# RX.net
KiCad netlist of a schematic drawn in Altium Designer
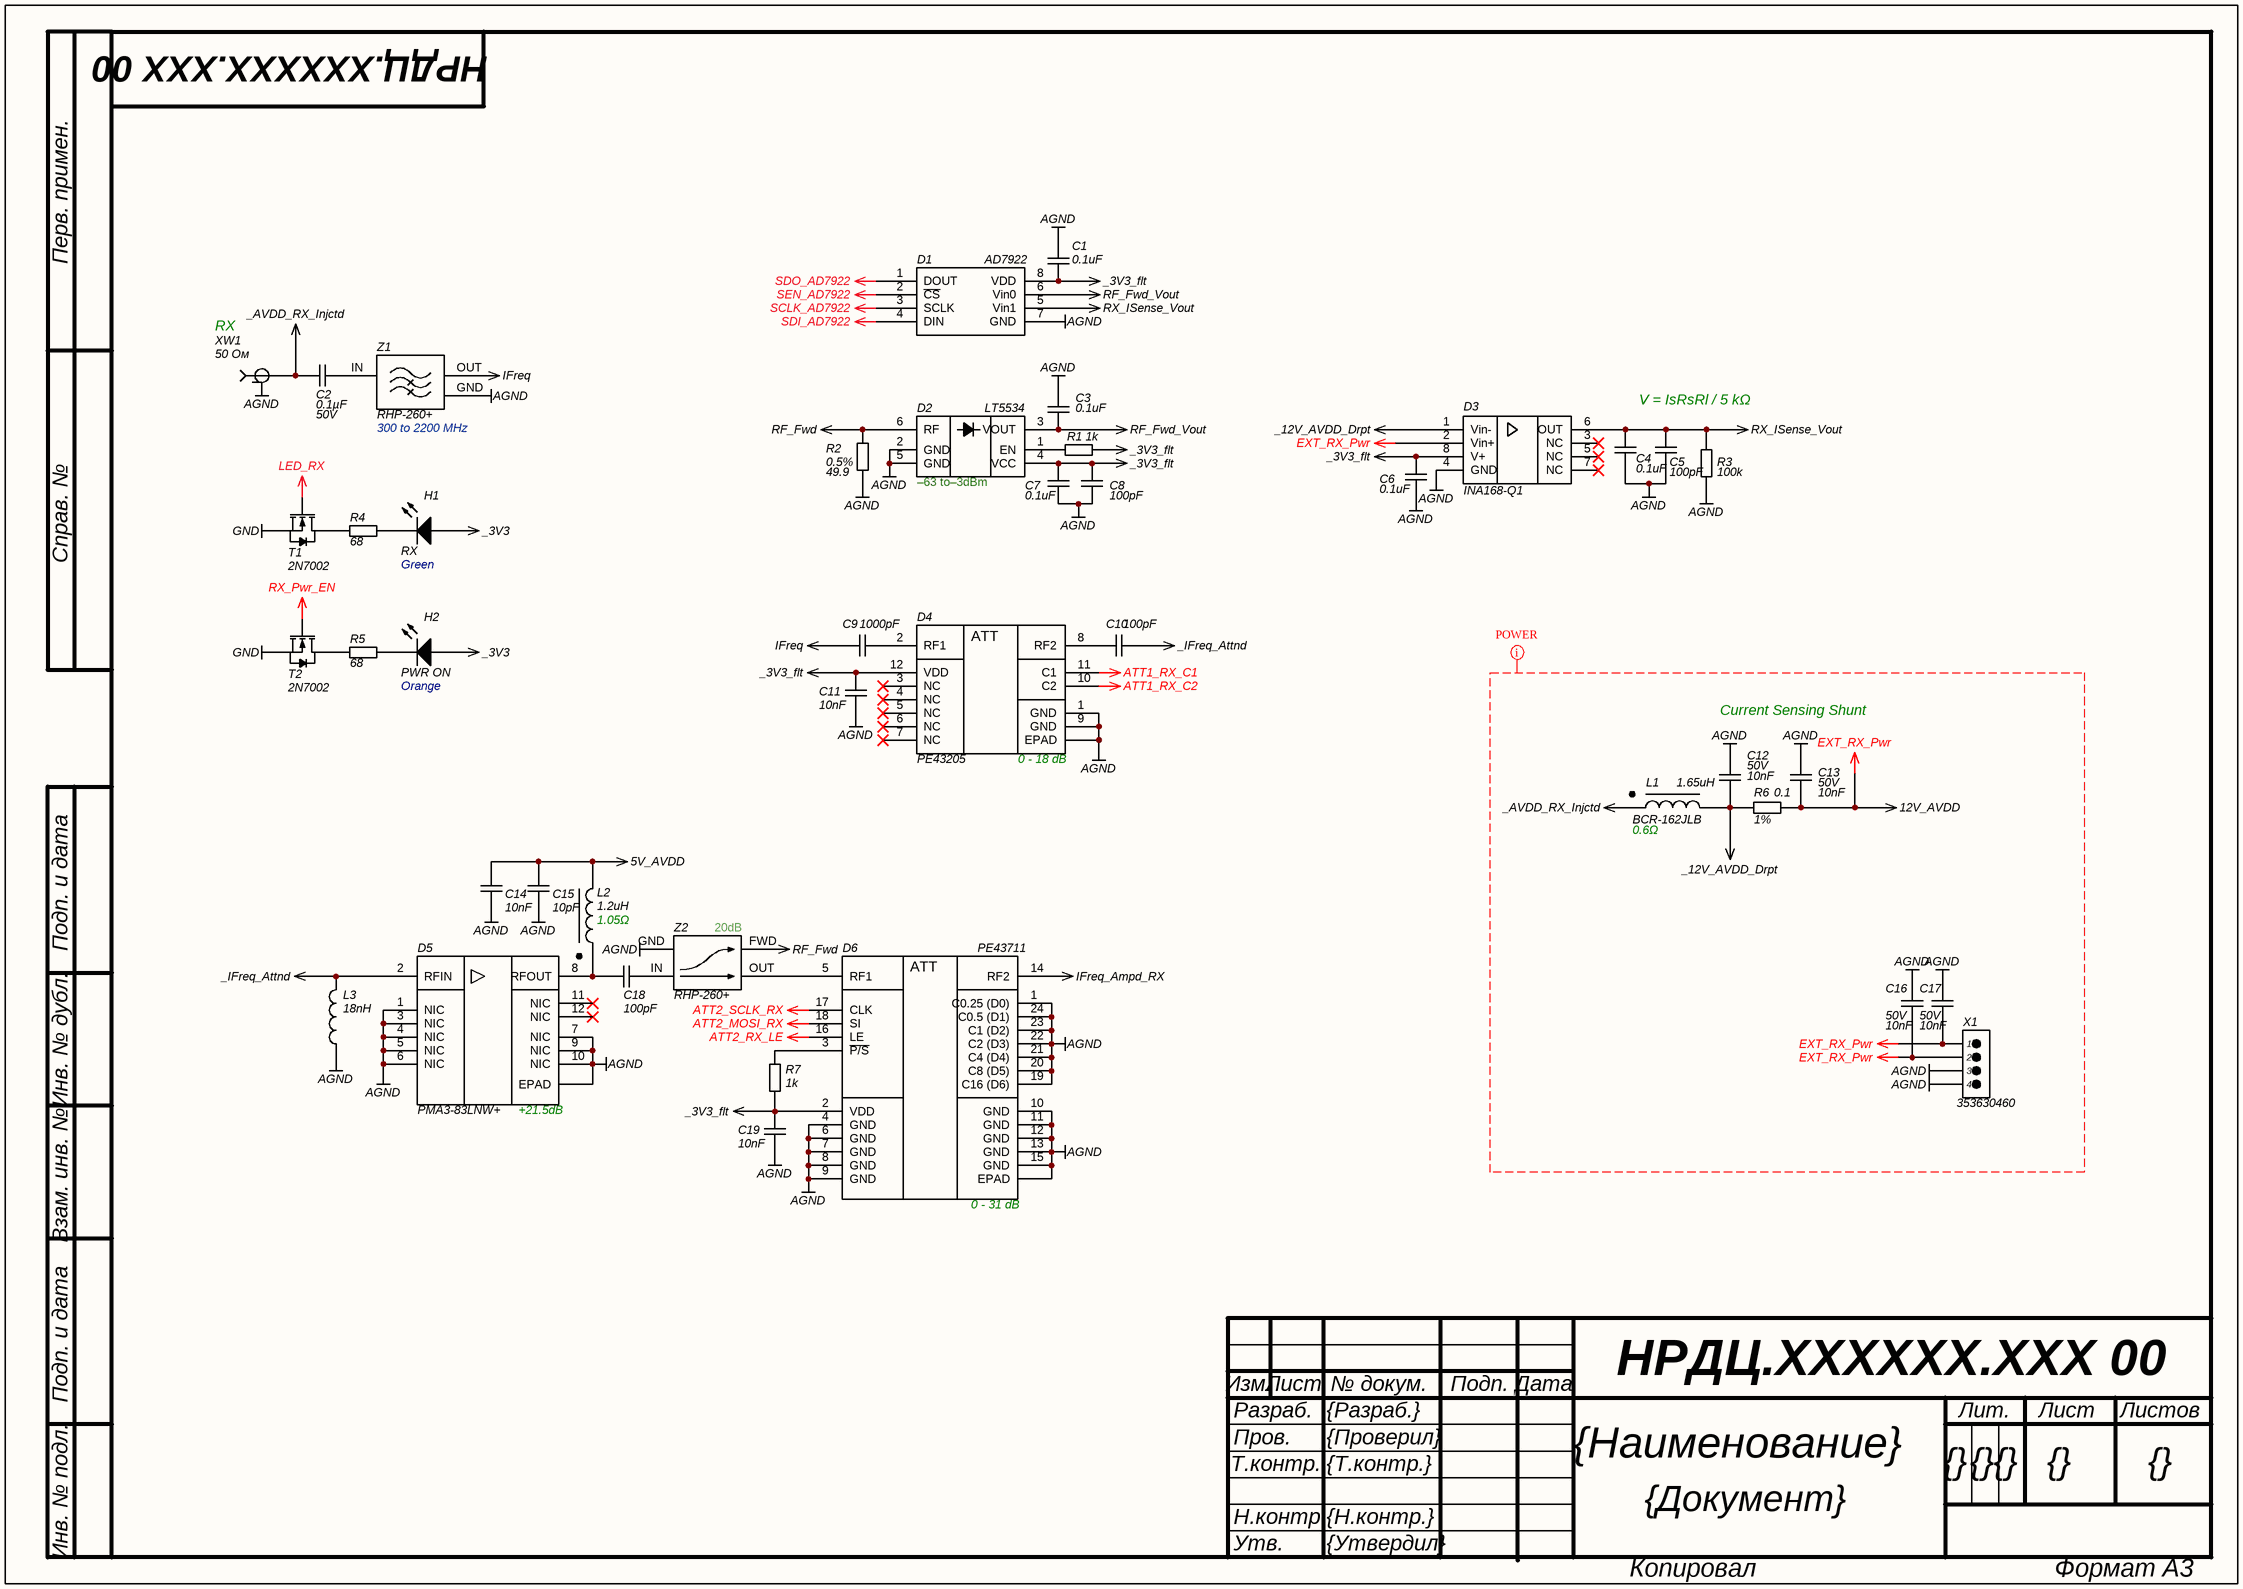
[diagram p0: RX.SchDoc]

(export (version "E")
  (design (tool "Eeschema 10.0.6"))
  (components
    (comp (ref "C1")
      (value "0.1uF")
      (footprint "C0402")
      (description "SMD Capacitor")
      (fields (field (name "MANUFACTURER") "Murata") (field (name "TOLERANCE") "10%"))
      (libsource (lib "Kintex_SDR") (part "CAP"))
    )
    (comp (ref "C2")
      (value "0.1µF")
      (footprint "C1206")
      (description "SMD Capacitor")
      (fields
        (field (name "MANUFACTURER") "Murata")
        (field (name "TOLERANCE") "5%")
        (field (name "VOLTAGE") "50V")
      )
      (libsource (lib "Kintex_SDR") (part "CAP"))
    )
    (comp (ref "C3")
      (value "0.1uF")
      (footprint "C0402")
      (description "SMD Capacitor")
      (fields (field (name "MANUFACTURER") "Murata") (field (name "TOLERANCE") "10%"))
      (libsource (lib "Kintex_SDR") (part "CAP"))
    )
    (comp (ref "C4")
      (value "0.1uF")
      (footprint "C0402")
      (description "SMD Capacitor")
      (fields (field (name "MANUFACTURER") "Murata") (field (name "TOLERANCE") "10%"))
      (libsource (lib "Kintex_SDR") (part "CAP"))
    )
    (comp (ref "C5")
      (value "100pF")
      (footprint "C0402")
      (description "SMD Capacitor")
      (fields (field (name "MANUFACTURER") "Murata") (field (name "TOLERANCE") "1%"))
      (libsource (lib "Kintex_SDR") (part "CAP"))
    )
    (comp (ref "C6")
      (value "0.1uF")
      (footprint "C0402")
      (description "SMD Capacitor")
      (fields (field (name "MANUFACTURER") "Murata") (field (name "TOLERANCE") "10%"))
      (libsource (lib "Kintex_SDR") (part "CAP"))
    )
    (comp (ref "C7")
      (value "0.1uF")
      (footprint "C0402")
      (description "SMD Capacitor")
      (fields (field (name "MANUFACTURER") "Murata") (field (name "TOLERANCE") "10%"))
      (libsource (lib "Kintex_SDR") (part "CAP"))
    )
    (comp (ref "C8")
      (value "100pF")
      (footprint "C0402")
      (description "SMD Capacitor")
      (fields (field (name "MANUFACTURER") "Murata") (field (name "TOLERANCE") "1%"))
      (libsource (lib "Kintex_SDR") (part "CAP"))
    )
    (comp (ref "C9")
      (value "1000pF")
      (footprint "C0402")
      (description "SMD Capacitor")
      (fields (field (name "MANUFACTURER") "Murata") (field (name "TOLERANCE") "5%"))
      (libsource (lib "Kintex_SDR") (part "CAP"))
    )
    (comp (ref "C10")
      (value "100pF")
      (footprint "C0402")
      (description "SMD Capacitor")
      (fields (field (name "MANUFACTURER") "Murata") (field (name "TOLERANCE") "1%"))
      (libsource (lib "Kintex_SDR") (part "CAP"))
    )
    (comp (ref "C11")
      (value "10nF")
      (footprint "C0402")
      (description "SMD Capacitor")
      (fields (field (name "MANUFACTURER") "Murata") (field (name "TOLERANCE") "10%"))
      (libsource (lib "Kintex_SDR") (part "CAP"))
    )
    (comp (ref "C12")
      (value "10nF")
      (footprint "C0402")
      (description "SMD Capacitor")
      (fields
        (field (name "MANUFACTURER") "Murata")
        (field (name "TOLERANCE") "5%")
        (field (name "VOLTAGE") "50V")
      )
      (libsource (lib "Kintex_SDR") (part "CAP"))
    )
    (comp (ref "C13")
      (value "10nF")
      (footprint "C0402")
      (description "SMD Capacitor")
      (fields
        (field (name "MANUFACTURER") "Murata")
        (field (name "TOLERANCE") "5%")
        (field (name "VOLTAGE") "50V")
      )
      (libsource (lib "Kintex_SDR") (part "CAP"))
    )
    (comp (ref "C14")
      (value "10nF")
      (footprint "C0402")
      (description "SMD Capacitor")
      (fields (field (name "MANUFACTURER") "Murata") (field (name "TOLERANCE") "10%"))
      (libsource (lib "Kintex_SDR") (part "CAP"))
    )
    (comp (ref "C15")
      (value "10pF")
      (footprint "C0402")
      (description "SMD Capacitor")
      (fields (field (name "MANUFACTURER") "Murata") (field (name "TOLERANCE") "1%"))
      (libsource (lib "Kintex_SDR") (part "CAP"))
    )
    (comp (ref "C16")
      (value "10nF")
      (footprint "C0402")
      (description "SMD Capacitor")
      (fields
        (field (name "MANUFACTURER") "Murata")
        (field (name "TOLERANCE") "5%")
        (field (name "VOLTAGE") "50V")
      )
      (libsource (lib "Kintex_SDR") (part "CAP"))
    )
    (comp (ref "C17")
      (value "10nF")
      (footprint "C0402")
      (description "SMD Capacitor")
      (fields
        (field (name "MANUFACTURER") "Murata")
        (field (name "TOLERANCE") "5%")
        (field (name "VOLTAGE") "50V")
      )
      (libsource (lib "Kintex_SDR") (part "CAP"))
    )
    (comp (ref "C18")
      (value "100pF")
      (footprint "C0402")
      (description "SMD Capacitor")
      (fields (field (name "MANUFACTURER") "Murata") (field (name "TOLERANCE") "1%"))
      (libsource (lib "Kintex_SDR") (part "CAP"))
    )
    (comp (ref "C19")
      (value "10nF")
      (footprint "C0402")
      (description "SMD Capacitor")
      (fields (field (name "MANUFACTURER") "Murata") (field (name "TOLERANCE") "10%"))
      (libsource (lib "Kintex_SDR") (part "CAP"))
    )
    (comp (ref "D1")
      (value "AD7922")
      (footprint "MSOP-8")
      (description "1 MSPS, 10-/12-Bit ADC")
      (fields (field (name "MANUFACTURER") "Analog Device") (field (name "VOLTAGE") "2.35 V to 5.25 V"))
      (libsource (lib "Kintex_SDR") (part "AD79x2"))
    )
    (comp (ref "D2")
      (value "LT5534")
      (footprint "DBLib:SC70")
      (description "50MHz to 3GHz monolithic RF power\r\ndetector")
      (fields
        (field (name "MANUFACTURER") "Linear Technology")
        (field (name "VOLTAGE") "Single 2.7V to 5.25V")
        (field (name "RF INPUT POWER RANGE") "–63 to–3dBm")
      )
      (libsource (lib "DBLib") (part "LT5534"))
    )
    (comp (ref "D3")
      (value "INA168-Q1")
      (footprint "DBLib:TSSOP (8)")
      (description "Automotive-Grade, High-Side, Current-Output, Current-Shunt Monitor")
      (fields (field (name "MANUFACTURER") "Texas Instruments") (field (name "VOLTAGE") "2.7 V to 60 V"))
      (libsource (lib "DBLib") (part "INA168-Q1"))
    )
    (comp (ref "D4")
      (value "PE43205")
      (footprint "DBLib:QFN-12")
      (description "50Ω, HaRP™ technology-enhanced\r\nfast switching 2-bit RF Digital Step Attenuator")
      (fields (field (name "MANUFACTURER") "Peregrine Technical Solutions"))
      (libsource (lib "DBLib") (part "PE43205"))
    )
    (comp (ref "D5")
      (value "PMA3-83LNW+")
      (footprint "DQ1225")
      (description "PHEMT based wideband, low noise MMIC amplifier")
      (fields (field (name "MANUFACTURER") "Mini-Circuits"))
      (libsource (lib "DBLib") (part "PMA3-83LNW+"))
    )
    (comp (ref "D6")
      (value "PE43711")
      (footprint "QFN-24")
      (description "The PE43711 is a 50Ω, HaRP™ technology-enhanced, 7-bit RF digital step attenuator")
      (fields (field (name "MANUFACTURER") "Peregrine Technical Solutions"))
      (libsource (lib "DBLib") (part "PE43711"))
    )
    (comp (ref "H1")
      (value "RX")
      (footprint "LED")
      (description "CHIP LED LAMP")
      (fields (field (name "MANUFACTURER") "Kingbright") (field (name "COLOR") "Green"))
      (libsource (lib "DBLib") (part "LED"))
    )
    (comp (ref "H2")
      (value "PWR ON")
      (footprint "LED")
      (description "CHIP LED LAMP")
      (fields (field (name "MANUFACTURER") "Kingbright") (field (name "COLOR") "Orange"))
      (libsource (lib "DBLib") (part "LED"))
    )
    (comp (ref "L1")
      (value "BCR-162JLB")
      (footprint "DBLib:BCR-162")
      (description "Broadband Conical Inductor")
      (fields
        (field (name "MANUFACTURER") "Coilcraft")
        (field (name "TOLERANCE") "±5%")
        (field (name "ALTIUM_VALUE") "1.65uH")
        (field (name "DCR") "0.6Ω")
      )
      (libsource (lib "DBLib") (part "Inductor_BCR"))
    )
    (comp (ref "L2")
      (value "1.2uH")
      (footprint "DBLib:BCR-122")
      (description "Broadband Conical Inductor")
      (fields
        (field (name "MANUFACTURER") "Coilcraft")
        (field (name "TOLERANCE") "±5%")
        (field (name "DCR") "1.05Ω")
      )
      (libsource (lib "DBLib") (part "Inductor_BCR"))
    )
    (comp (ref "L3")
      (value "18nH")
      (footprint "DBLib:L0603_HP")
      (description "Chip SMD Inductor")
      (fields (field (name "MANUFACTURER") "Coilcraft") (field (name "TOLERANCE") "5%"))
      (libsource (lib "DBLib") (part "Inductor RF"))
    )
    (comp (ref "R1")
      (value "1k")
      (footprint "R0402")
      (description "SMD Resistor")
      (fields (field (name "POWER") "0.062 Wt") (field (name "TOLERANCE") "5%"))
      (libsource (lib "Kintex_SDR") (part "RES"))
    )
    (comp (ref "R2")
      (value "49.9")
      (footprint "R0402")
      (description "SMD Resistor")
      (fields
        (field (name "POWER") "0.063 Wt")
        (field (name "TOLERANCE") "0.5%")
        (field (name "MANUFACTURER") "Panasonic Electronic Components")
      )
      (libsource (lib "") (part "RES_1"))
    )
    (comp (ref "R3")
      (value "100k")
      (footprint "R0402")
      (description "SMD Resistor")
      (fields (field (name "POWER") "1/5 Wt") (field (name "TOLERANCE") "1%"))
      (libsource (lib "") (part "RES_2"))
    )
    (comp (ref "R4")
      (value "68")
      (footprint "R0402")
      (description "SMD Resistor")
      (fields (field (name "POWER") "0.062 Wt") (field (name "TOLERANCE") "5%"))
      (libsource (lib "") (part "RES_3"))
    )
    (comp (ref "R5")
      (value "68")
      (footprint "R0402")
      (description "SMD Resistor")
      (fields (field (name "POWER") "0.062 Wt") (field (name "TOLERANCE") "5%"))
      (libsource (lib "Kintex_SDR") (part "RES"))
    )
    (comp (ref "R6")
      (value "0.1")
      (footprint "R0805")
      (description "SMD Resistor")
      (fields
        (field (name "POWER") "1/2 Wt")
        (field (name "TOLERANCE") "1%")
        (field (name "MANUFACTURER") "Panasonic Electronic Components")
      )
      (libsource (lib "Kintex_SDR") (part "RES"))
    )
    (comp (ref "R7")
      (value "1k")
      (footprint "R0402")
      (description "SMD Resistor")
      (fields (field (name "POWER") "0.062 Wt") (field (name "TOLERANCE") "5%"))
      (libsource (lib "") (part "RES_2"))
    )
    (comp (ref "T1")
      (value "2N7002")
      (footprint "SOT-23")
      (description "N-Channel MOSFET 2N7002")
      (fields (field (name "VOLTAGE") "60V"))
      (libsource (lib "Kintex_SDR") (part "2N7002"))
    )
    (comp (ref "T2")
      (value "2N7002")
      (footprint "SOT-23")
      (description "N-Channel MOSFET 2N7002")
      (fields (field (name "VOLTAGE") "60V"))
      (libsource (lib "Kintex_SDR") (part "2N7002"))
    )
    (comp (ref "X1")
      (value "353630460")
      (footprint "DBLib:CON_353630460")
      (description "2.00mm Pitch Sherlock Wire-to-Board Header, Right-Angle, with Positive Lock, 4 Circuits")
      (fields (field (name "MANUFACTURER") "Molex"))
      (libsource (lib "DBLib") (part "353630460"))
    )
    (comp (ref "XW1")
      (value "50 Ом")
      (footprint "MOLEX SD-73251-135 (Gold)")
      (description "50 Ohms, SMA Jack, Vertica")
      (fields (field (name "MANUFACTURER") "Molex"))
      (libsource (lib "DBLib") (part "RF Connector"))
    )
    (comp (ref "Z1")
      (value "RHP-260+")
      (footprint "GP731")
      (description "High Pass Filter")
      (fields (field (name "MANUFACTURER") "Mini-Circuits") (field (name "FREQUENCY") "300 to 2200 MHz"))
      (libsource (lib "DBLib") (part "RHP-260+"))
    )
    (comp (ref "Z2")
      (value "RHP-260+")
      (footprint "DBLib:AH202")
      (description "Directional Coupler")
      (fields (field (name "MANUFACTURER") "Mini-Circuits") (field (name "COUPLING") "20dB"))
      (libsource (lib "DBLib") (part "SYD-20-33+"))
    )
  )
  (nets
    (net (code "1") (name "5V_AVDD") (class "Default")
      (node (ref "C14") (pin "2") (pinfunction "2_2") (pintype "passive"))
      (node (ref "C15") (pin "2") (pinfunction "2_2") (pintype "passive"))
      (node (ref "L2") (pin "2") (pinfunction "2_2") (pintype "passive"))
    )
    (net (code "2") (name "12V_AVDD") (class "Default")
      (node (ref "C13") (pin "1") (pinfunction "1_1") (pintype "passive"))
      (node (ref "C16") (pin "2") (pinfunction "2_2") (pintype "passive"))
      (node (ref "C17") (pin "2") (pinfunction "2_2") (pintype "passive"))
      (node (ref "D3") (pin "2") (pinfunction "Vin+_2") (pintype "passive"))
      (node (ref "R6") (pin "1") (pinfunction "1_1") (pintype "passive"))
      (node (ref "X1") (pin "1") (pinfunction "1_1") (pintype "passive"))
      (node (ref "X1") (pin "2") (pinfunction "2_2") (pintype "passive"))
    )
    (net (code "3") (name "AGND") (class "Default")
      (node (ref "C1") (pin "2") (pinfunction "2_2") (pintype "passive"))
      (node (ref "C11") (pin "1") (pinfunction "1_1") (pintype "passive"))
      (node (ref "C12") (pin "2") (pinfunction "2_2") (pintype "passive"))
      (node (ref "C13") (pin "2") (pinfunction "2_2") (pintype "passive"))
      (node (ref "C14") (pin "1") (pinfunction "1_1") (pintype "passive"))
      (node (ref "C15") (pin "1") (pinfunction "1_1") (pintype "passive"))
      (node (ref "C16") (pin "1") (pinfunction "1_1") (pintype "passive"))
      (node (ref "C17") (pin "1") (pinfunction "1_1") (pintype "passive"))
      (node (ref "C19") (pin "1") (pinfunction "1_1") (pintype "passive"))
      (node (ref "C3") (pin "1") (pinfunction "1_1") (pintype "passive"))
      (node (ref "C4") (pin "1") (pinfunction "1_1") (pintype "passive"))
      (node (ref "C5") (pin "1") (pinfunction "1_1") (pintype "passive"))
      (node (ref "C6") (pin "1") (pinfunction "1_1") (pintype "passive"))
      (node (ref "C7") (pin "1") (pinfunction "1_1") (pintype "passive"))
      (node (ref "C8") (pin "1") (pinfunction "1_1") (pintype "passive"))
      (node (ref "D1") (pin "7") (pinfunction "GND_7") (pintype "passive"))
      (node (ref "D2") (pin "2") (pinfunction "GND_2") (pintype "passive"))
      (node (ref "D2") (pin "5") (pinfunction "GND_5") (pintype "passive"))
      (node (ref "D3") (pin "4") (pinfunction "GND_4") (pintype "passive"))
      (node (ref "D4") (pin "1") (pinfunction "GND_1") (pintype "passive"))
      (node (ref "D4") (pin "13") (pinfunction "EPAD_13") (pintype "passive"))
      (node (ref "D4") (pin "9") (pinfunction "GND_9") (pintype "passive"))
      (node (ref "D5") (pin "1") (pinfunction "NIC_1") (pintype "passive"))
      (node (ref "D5") (pin "10") (pinfunction "NIC_10") (pintype "passive"))
      (node (ref "D5") (pin "13") (pinfunction "EPAD_13") (pintype "passive"))
      (node (ref "D5") (pin "3") (pinfunction "NIC_3") (pintype "passive"))
      (node (ref "D5") (pin "4") (pinfunction "NIC_4") (pintype "passive"))
      (node (ref "D5") (pin "5") (pinfunction "NIC_5") (pintype "passive"))
      (node (ref "D5") (pin "6") (pinfunction "NIC_6") (pintype "passive"))
      (node (ref "D5") (pin "7") (pinfunction "NIC_7") (pintype "passive"))
      (node (ref "D5") (pin "9") (pinfunction "NIC_9") (pintype "passive"))
      (node (ref "D6") (pin "1") (pinfunction "C0.25_(D0)_1") (pintype "passive"))
      (node (ref "D6") (pin "10") (pinfunction "GND_10") (pintype "passive"))
      (node (ref "D6") (pin "11") (pinfunction "GND_11") (pintype "passive"))
      (node (ref "D6") (pin "12") (pinfunction "GND_12") (pintype "passive"))
      (node (ref "D6") (pin "13") (pinfunction "GND_13") (pintype "passive"))
      (node (ref "D6") (pin "15") (pinfunction "GND_15") (pintype "passive"))
      (node (ref "D6") (pin "19") (pinfunction "C16_(D6)_19") (pintype "passive"))
      (node (ref "D6") (pin "20") (pinfunction "C8_(D5)_20") (pintype "passive"))
      (node (ref "D6") (pin "21") (pinfunction "C4_(D4)_21") (pintype "passive"))
      (node (ref "D6") (pin "22") (pinfunction "C2_(D3)_22") (pintype "passive"))
      (node (ref "D6") (pin "23") (pinfunction "C1_(D2)_23") (pintype "passive"))
      (node (ref "D6") (pin "24") (pinfunction "C0.5_(D1)_24") (pintype "passive"))
      (node (ref "D6") (pin "25") (pinfunction "EPAD_25") (pintype "passive"))
      (node (ref "D6") (pin "4") (pinfunction "GND_4") (pintype "passive"))
      (node (ref "D6") (pin "6") (pinfunction "GND_6") (pintype "passive"))
      (node (ref "D6") (pin "7") (pinfunction "GND_7") (pintype "passive"))
      (node (ref "D6") (pin "8") (pinfunction "GND_8") (pintype "passive"))
      (node (ref "D6") (pin "9") (pinfunction "GND_9") (pintype "passive"))
      (node (ref "L3") (pin "1") (pinfunction "1_1") (pintype "passive"))
      (node (ref "R2") (pin "2") (pinfunction "2_2") (pintype "passive"))
      (node (ref "R3") (pin "1") (pinfunction "1_1") (pintype "passive"))
      (node (ref "X1") (pin "3") (pinfunction "3_3") (pintype "passive"))
      (node (ref "X1") (pin "4") (pinfunction "4_4") (pintype "passive"))
      (node (ref "XW1") (pin "G") (pinfunction "GND_G") (pintype "passive"))
      (node (ref "Z1") (pin "GND") (pinfunction "GND_GND") (pintype "passive"))
    )
    (net (code "4") (name "ATT1_RX_C1") (class "Default")
      (node (ref "D4") (pin "11") (pinfunction "C1_11") (pintype "passive"))
    )
    (net (code "5") (name "ATT1_RX_C2") (class "Default")
      (node (ref "D4") (pin "10") (pinfunction "C2_10") (pintype "passive"))
    )
    (net (code "6") (name "ATT2_MOSI_RX") (class "Default")
      (node (ref "D6") (pin "18") (pinfunction "SI_18") (pintype "passive"))
    )
    (net (code "7") (name "ATT2_RX_LE") (class "Default")
      (node (ref "D6") (pin "16") (pinfunction "LE_16") (pintype "passive"))
    )
    (net (code "8") (name "ATT2_SCLK_RX") (class "Default")
      (node (ref "D6") (pin "17") (pinfunction "CLK_17") (pintype "passive"))
    )
    (net (code "9") (name "GND") (class "Default")
      (node (ref "T1") (pin "2") (pinfunction "S_2") (pintype "passive"))
      (node (ref "T2") (pin "2") (pinfunction "S_2") (pintype "passive"))
    )
    (net (code "10") (name "IFreq") (class "Default")
      (node (ref "C9") (pin "1") (pinfunction "1_1") (pintype "passive"))
      (node (ref "Z1") (pin "OUT") (pinfunction "OUT_OUT") (pintype "passive"))
    )
    (net (code "11") (name "IFreq_Ampd_RX") (class "Default")
      (node (ref "D6") (pin "14") (pinfunction "RF2_14") (pintype "passive"))
    )
    (net (code "12") (name "LED_RX") (class "Default")
      (node (ref "T1") (pin "1") (pinfunction "G_1") (pintype "passive"))
    )
    (net (code "13") (name "Net-(C2-Pad2)") (class "Default")
      (node (ref "C2") (pin "2") (pinfunction "2_2") (pintype "passive"))
      (node (ref "Z1") (pin "IN") (pinfunction "IN_IN") (pintype "passive"))
    )
    (net (code "14") (name "Net-(C18-Pad2)") (class "Default")
      (node (ref "C18") (pin "2") (pinfunction "2_2") (pintype "passive"))
      (node (ref "Z2") (pin "IN") (pinfunction "IN_IN") (pintype "passive"))
    )
    (net (code "15") (name "Net-(D2-EN)") (class "Default")
      (node (ref "D2") (pin "1") (pinfunction "EN_1") (pintype "passive"))
      (node (ref "R1") (pin "2") (pinfunction "2_2") (pintype "passive"))
    )
    (net (code "16") (name "Net-(D4-RF1)") (class "Default")
      (node (ref "C9") (pin "2") (pinfunction "2_2") (pintype "passive"))
      (node (ref "D4") (pin "2") (pinfunction "RF1_2") (pintype "passive"))
    )
    (net (code "17") (name "Net-(D4-RF2)") (class "Default")
      (node (ref "C10") (pin "1") (pinfunction "1_1") (pintype "passive"))
      (node (ref "D4") (pin "8") (pinfunction "RF2_8") (pintype "passive"))
    )
    (net (code "18") (name "Net-(D5-RFOUT)") (class "Default")
      (node (ref "C18") (pin "1") (pinfunction "1_1") (pintype "passive"))
      (node (ref "D5") (pin "8") (pinfunction "RFOUT_8") (pintype "passive"))
      (node (ref "L2") (pin "1") (pinfunction "1_1") (pintype "passive"))
    )
    (net (code "19") (name "Net-(D6-RF1)") (class "Default")
      (node (ref "D6") (pin "5") (pinfunction "RF1_5") (pintype "passive"))
      (node (ref "Z2") (pin "OUT") (pinfunction "OUT_OUT") (pintype "passive"))
    )
    (net (code "20") (name "Net-(D6-~{P{slash}S})") (class "Default")
      (node (ref "D6") (pin "3") (pinfunction "~{P/S}_3") (pintype "passive"))
      (node (ref "R7") (pin "2") (pinfunction "2_2") (pintype "passive"))
    )
    (net (code "21") (name "Net-(H1-K)") (class "Default")
      (node (ref "H1") (pin "1") (pinfunction "K_1") (pintype "passive"))
      (node (ref "R4") (pin "2") (pinfunction "2_2") (pintype "passive"))
    )
    (net (code "22") (name "Net-(H2-K)") (class "Default")
      (node (ref "H2") (pin "1") (pinfunction "K_1") (pintype "passive"))
      (node (ref "R5") (pin "1") (pinfunction "1_1") (pintype "passive"))
    )
    (net (code "23") (name "Net-(T1-D)") (class "Default")
      (node (ref "R4") (pin "1") (pinfunction "1_1") (pintype "passive"))
      (node (ref "T1") (pin "3") (pinfunction "D_3") (pintype "passive"))
    )
    (net (code "24") (name "Net-(T2-D)") (class "Default")
      (node (ref "R5") (pin "2") (pinfunction "2_2") (pintype "passive"))
      (node (ref "T2") (pin "3") (pinfunction "D_3") (pintype "passive"))
    )
    (net (code "25") (name "RF_Fwd") (class "Default")
      (node (ref "D2") (pin "6") (pinfunction "RF_6") (pintype "passive"))
      (node (ref "R2") (pin "1") (pinfunction "1_1") (pintype "passive"))
      (node (ref "Z2") (pin "FWD") (pinfunction "FWD_FWD") (pintype "passive"))
    )
    (net (code "26") (name "RF_Fwd_Vout") (class "Default")
      (node (ref "C3") (pin "2") (pinfunction "2_2") (pintype "passive"))
      (node (ref "D1") (pin "6") (pinfunction "Vin0_6") (pintype "passive"))
      (node (ref "D2") (pin "3") (pinfunction "VOUT_3") (pintype "passive"))
    )
    (net (code "27") (name "RX_ISense_Vout") (class "Default")
      (node (ref "C4") (pin "2") (pinfunction "2_2") (pintype "passive"))
      (node (ref "C5") (pin "2") (pinfunction "2_2") (pintype "passive"))
      (node (ref "D1") (pin "5") (pinfunction "Vin1_5") (pintype "passive"))
      (node (ref "D3") (pin "6") (pinfunction "OUT_6") (pintype "passive"))
      (node (ref "R3") (pin "2") (pinfunction "2_2") (pintype "passive"))
    )
    (net (code "28") (name "RX_Pwr_EN") (class "Default")
      (node (ref "T2") (pin "1") (pinfunction "G_1") (pintype "passive"))
    )
    (net (code "29") (name "SCLK_AD7922") (class "Default")
      (node (ref "D1") (pin "3") (pinfunction "SCLK_3") (pintype "passive"))
    )
    (net (code "30") (name "SDI_AD7922") (class "Default")
      (node (ref "D1") (pin "4") (pinfunction "DIN_4") (pintype "passive"))
    )
    (net (code "31") (name "SDO_AD7922") (class "Default")
      (node (ref "D1") (pin "1") (pinfunction "DOUT_1") (pintype "passive"))
    )
    (net (code "32") (name "SEN_AD7922") (class "Default")
      (node (ref "D1") (pin "2") (pinfunction "~{CS}_2") (pintype "passive"))
    )
    (net (code "33") (name "_3V3") (class "Default")
      (node (ref "H1") (pin "2") (pinfunction "A_2") (pintype "passive"))
      (node (ref "H2") (pin "2") (pinfunction "A_2") (pintype "passive"))
    )
    (net (code "34") (name "_3V3_flt") (class "Default")
      (node (ref "C1") (pin "1") (pinfunction "1_1") (pintype "passive"))
      (node (ref "C11") (pin "2") (pinfunction "2_2") (pintype "passive"))
      (node (ref "C19") (pin "2") (pinfunction "2_2") (pintype "passive"))
      (node (ref "C6") (pin "2") (pinfunction "2_2") (pintype "passive"))
      (node (ref "C7") (pin "2") (pinfunction "2_2") (pintype "passive"))
      (node (ref "C8") (pin "2") (pinfunction "2_2") (pintype "passive"))
      (node (ref "D1") (pin "8") (pinfunction "VDD_8") (pintype "passive"))
      (node (ref "D2") (pin "4") (pinfunction "VCC_4") (pintype "passive"))
      (node (ref "D3") (pin "8") (pinfunction "V+_8") (pintype "passive"))
      (node (ref "D4") (pin "12") (pinfunction "VDD_12") (pintype "passive"))
      (node (ref "D6") (pin "2") (pinfunction "VDD_2") (pintype "passive"))
      (node (ref "R1") (pin "1") (pinfunction "1_1") (pintype "passive"))
      (node (ref "R7") (pin "1") (pinfunction "1_1") (pintype "passive"))
    )
    (net (code "35") (name "_12V_AVDD_Drpt") (class "Default")
      (node (ref "C12") (pin "1") (pinfunction "1_1") (pintype "passive"))
      (node (ref "D3") (pin "1") (pinfunction "Vin-_1") (pintype "passive"))
      (node (ref "L1") (pin "2") (pinfunction "2_2") (pintype "passive"))
      (node (ref "R6") (pin "2") (pinfunction "2_2") (pintype "passive"))
    )
    (net (code "36") (name "_AVDD_RX_Injctd") (class "Default")
      (node (ref "C2") (pin "1") (pinfunction "1_1") (pintype "passive"))
      (node (ref "L1") (pin "1") (pinfunction "1_1") (pintype "passive"))
      (node (ref "XW1") (pin "S") (pinfunction "RF_S") (pintype "passive"))
    )
    (net (code "37") (name "_IFreq_Attnd") (class "Default")
      (node (ref "C10") (pin "2") (pinfunction "2_2") (pintype "passive"))
      (node (ref "D5") (pin "2") (pinfunction "RFIN_2") (pintype "passive"))
      (node (ref "L3") (pin "2") (pinfunction "2_2") (pintype "passive"))
    )
    (net (code "38") (name "unconnected-(D3-NC-Pad3)") (class "Default")
      (node (ref "D3") (pin "3") (pinfunction "NC_3") (pintype "passive+no_connect"))
    )
    (net (code "39") (name "unconnected-(D3-NC-Pad5)") (class "Default")
      (node (ref "D3") (pin "5") (pinfunction "NC_5") (pintype "passive+no_connect"))
    )
    (net (code "40") (name "unconnected-(D3-NC-Pad7)") (class "Default")
      (node (ref "D3") (pin "7") (pinfunction "NC_7") (pintype "passive+no_connect"))
    )
    (net (code "41") (name "unconnected-(D4-NC-Pad3)") (class "Default")
      (node (ref "D4") (pin "3") (pinfunction "NC_3") (pintype "passive+no_connect"))
    )
    (net (code "42") (name "unconnected-(D4-NC-Pad4)") (class "Default")
      (node (ref "D4") (pin "4") (pinfunction "NC_4") (pintype "passive+no_connect"))
    )
    (net (code "43") (name "unconnected-(D4-NC-Pad5)") (class "Default")
      (node (ref "D4") (pin "5") (pinfunction "NC_5") (pintype "passive+no_connect"))
    )
    (net (code "44") (name "unconnected-(D4-NC-Pad6)") (class "Default")
      (node (ref "D4") (pin "6") (pinfunction "NC_6") (pintype "passive+no_connect"))
    )
    (net (code "45") (name "unconnected-(D4-NC-Pad7)") (class "Default")
      (node (ref "D4") (pin "7") (pinfunction "NC_7") (pintype "passive+no_connect"))
    )
    (net (code "46") (name "unconnected-(D5-NIC-Pad11)") (class "Default")
      (node (ref "D5") (pin "11") (pinfunction "NIC_11") (pintype "passive+no_connect"))
    )
    (net (code "47") (name "unconnected-(D5-NIC-Pad12)") (class "Default")
      (node (ref "D5") (pin "12") (pinfunction "NIC_12") (pintype "passive+no_connect"))
    )
    (net (code "48") (name "unconnected-(Z2-PadGND)") (class "Default")
      (node (ref "Z2") (pin "GND") (pinfunction "GND_GND") (pintype "passive"))
    )
  )
)
